# LCD.net
KiCad netlist of a schematic drawn in Altium Designer
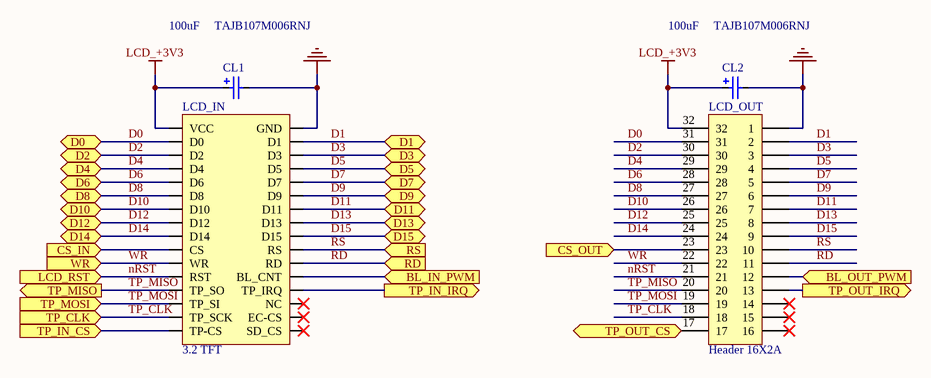
[diagram p0: LCD.SchDoc]

(export (version "E")
  (design (tool "Eeschema 10.0.6"))
  (components
    (comp (ref "CL1")
      (value "100uF     TAJB107M006RNJ")
      (footprint "CAP_TAN_B_3518")
      (description "Capacitor")
      (fields (field (name "Comment") "Cap_Tan"))
      (libsource (lib "Peace的集成库") (part "Cap_Tan"))
    )
    (comp (ref "CL2")
      (value "100uF     TAJB107M006RNJ")
      (footprint "CAP_TAN_B_3518")
      (description "Capacitor")
      (fields (field (name "Comment") "Cap_Tan"))
      (libsource (lib "Peace的集成库") (part "Cap_Tan"))
    )
    (comp (ref "LCD_IN") (value "3.2 TFT") (footprint "LCD3.2") (libsource (lib "Peace的集成库") (part "LCD3.2")))
    (comp (ref "LCD_OUT")
      (value "Header 16X2A")
      (footprint "HDR2X16_CEN")
      (description "Header, 16-Pin, Dual row")
      (fields (field (name "PUBLISHER") "Altium Limited"))
      (libsource (lib "Peace的集成库") (part "Header 16X2A"))
    )
  )
  (nets
    (net (code "1") (name "/BL_IN_PWM") (class "Default")
      (node (ref "LCD_IN") (pin "24") (pinfunction "BL_CNT_24") (pintype "passive"))
    )
    (net (code "2") (name "/BL_OUT_PWM") (class "Default")
      (node (ref "LCD_OUT") (pin "12") (pinfunction "12_12") (pintype "passive"))
    )
    (net (code "3") (name "/CS_IN") (class "Default")
      (node (ref "LCD_IN") (pin "19") (pinfunction "CS_19") (pintype "passive"))
    )
    (net (code "4") (name "/CS_OUT") (class "Default")
      (node (ref "LCD_OUT") (pin "23") (pinfunction "23_23") (pintype "passive"))
    )
    (net (code "5") (name "/D0") (class "Default")
      (node (ref "LCD_IN") (pin "3") (pinfunction "D0_3") (pintype "passive"))
      (node (ref "LCD_OUT") (pin "31") (pinfunction "31_31") (pintype "passive"))
    )
    (net (code "6") (name "/D1") (class "Default")
      (node (ref "LCD_IN") (pin "4") (pinfunction "D1_4") (pintype "passive"))
      (node (ref "LCD_OUT") (pin "2") (pinfunction "2_2") (pintype "passive"))
    )
    (net (code "7") (name "/D2") (class "Default")
      (node (ref "LCD_IN") (pin "5") (pinfunction "D2_5") (pintype "passive"))
      (node (ref "LCD_OUT") (pin "30") (pinfunction "30_30") (pintype "passive"))
    )
    (net (code "8") (name "/D3") (class "Default")
      (node (ref "LCD_IN") (pin "6") (pinfunction "D3_6") (pintype "passive"))
      (node (ref "LCD_OUT") (pin "3") (pinfunction "3_3") (pintype "passive"))
    )
    (net (code "9") (name "/D4") (class "Default")
      (node (ref "LCD_IN") (pin "7") (pinfunction "D4_7") (pintype "passive"))
      (node (ref "LCD_OUT") (pin "29") (pinfunction "29_29") (pintype "passive"))
    )
    (net (code "10") (name "/D5") (class "Default")
      (node (ref "LCD_IN") (pin "8") (pinfunction "D5_8") (pintype "passive"))
      (node (ref "LCD_OUT") (pin "4") (pinfunction "4_4") (pintype "passive"))
    )
    (net (code "11") (name "/D6") (class "Default")
      (node (ref "LCD_IN") (pin "9") (pinfunction "D6_9") (pintype "passive"))
      (node (ref "LCD_OUT") (pin "28") (pinfunction "28_28") (pintype "passive"))
    )
    (net (code "12") (name "/D7") (class "Default")
      (node (ref "LCD_IN") (pin "10") (pinfunction "D7_10") (pintype "passive"))
      (node (ref "LCD_OUT") (pin "5") (pinfunction "5_5") (pintype "passive"))
    )
    (net (code "13") (name "/D8") (class "Default")
      (node (ref "LCD_IN") (pin "11") (pinfunction "D8_11") (pintype "passive"))
      (node (ref "LCD_OUT") (pin "27") (pinfunction "27_27") (pintype "passive"))
    )
    (net (code "14") (name "/D9") (class "Default")
      (node (ref "LCD_IN") (pin "12") (pinfunction "D9_12") (pintype "passive"))
      (node (ref "LCD_OUT") (pin "6") (pinfunction "6_6") (pintype "passive"))
    )
    (net (code "15") (name "/D10") (class "Default")
      (node (ref "LCD_IN") (pin "13") (pinfunction "D10_13") (pintype "passive"))
      (node (ref "LCD_OUT") (pin "26") (pinfunction "26_26") (pintype "passive"))
    )
    (net (code "16") (name "/D11") (class "Default")
      (node (ref "LCD_IN") (pin "14") (pinfunction "D11_14") (pintype "passive"))
      (node (ref "LCD_OUT") (pin "7") (pinfunction "7_7") (pintype "passive"))
    )
    (net (code "17") (name "/D12") (class "Default")
      (node (ref "LCD_IN") (pin "15") (pinfunction "D12_15") (pintype "passive"))
      (node (ref "LCD_OUT") (pin "25") (pinfunction "25_25") (pintype "passive"))
    )
    (net (code "18") (name "/D13") (class "Default")
      (node (ref "LCD_IN") (pin "16") (pinfunction "D13_16") (pintype "passive"))
      (node (ref "LCD_OUT") (pin "8") (pinfunction "8_8") (pintype "passive"))
    )
    (net (code "19") (name "/D14") (class "Default")
      (node (ref "LCD_IN") (pin "17") (pinfunction "D14_17") (pintype "passive"))
      (node (ref "LCD_OUT") (pin "24") (pinfunction "24_24") (pintype "passive"))
    )
    (net (code "20") (name "/D15") (class "Default")
      (node (ref "LCD_IN") (pin "18") (pinfunction "D15_18") (pintype "passive"))
      (node (ref "LCD_OUT") (pin "9") (pinfunction "9_9") (pintype "passive"))
    )
    (net (code "21") (name "/RD") (class "Default")
      (node (ref "LCD_IN") (pin "22") (pinfunction "RD_22") (pintype "passive"))
      (node (ref "LCD_OUT") (pin "11") (pinfunction "11_11") (pintype "passive"))
    )
    (net (code "22") (name "/RS") (class "Default")
      (node (ref "LCD_IN") (pin "20") (pinfunction "RS_20") (pintype "passive"))
      (node (ref "LCD_OUT") (pin "10") (pinfunction "10_10") (pintype "passive"))
    )
    (net (code "23") (name "/TP_CLK") (class "Default")
      (node (ref "LCD_IN") (pin "29") (pinfunction "TP_SCK_29") (pintype "passive"))
      (node (ref "LCD_OUT") (pin "18") (pinfunction "18_18") (pintype "passive"))
    )
    (net (code "24") (name "/TP_IN_CS") (class "Default")
      (node (ref "LCD_IN") (pin "31") (pinfunction "TP-CS_31") (pintype "passive"))
    )
    (net (code "25") (name "/TP_IN_IRQ") (class "Default")
      (node (ref "LCD_IN") (pin "26") (pinfunction "TP_IRQ_26") (pintype "passive"))
    )
    (net (code "26") (name "/TP_MISO") (class "Default")
      (node (ref "LCD_IN") (pin "25") (pinfunction "TP_SO_25") (pintype "passive"))
      (node (ref "LCD_OUT") (pin "20") (pinfunction "20_20") (pintype "passive"))
    )
    (net (code "27") (name "/TP_MOSI") (class "Default")
      (node (ref "LCD_IN") (pin "27") (pinfunction "TP_SI_27") (pintype "passive"))
      (node (ref "LCD_OUT") (pin "19") (pinfunction "19_19") (pintype "passive"))
    )
    (net (code "28") (name "/TP_OUT_CS") (class "Default")
      (node (ref "LCD_OUT") (pin "17") (pinfunction "17_17") (pintype "passive"))
    )
    (net (code "29") (name "/TP_OUT_IRQ") (class "Default")
      (node (ref "LCD_OUT") (pin "13") (pinfunction "13_13") (pintype "passive"))
    )
    (net (code "30") (name "/WR") (class "Default")
      (node (ref "LCD_IN") (pin "21") (pinfunction "WR_21") (pintype "passive"))
      (node (ref "LCD_OUT") (pin "22") (pinfunction "22_22") (pintype "passive"))
    )
    (net (code "31") (name "/nRST") (class "Default")
      (node (ref "LCD_IN") (pin "23") (pinfunction "RST_23") (pintype "passive"))
      (node (ref "LCD_OUT") (pin "21") (pinfunction "21_21") (pintype "passive"))
    )
    (net (code "32") (name "GND") (class "Default")
      (node (ref "CL1") (pin "2") (pinfunction "2_2") (pintype "passive"))
      (node (ref "CL2") (pin "2") (pinfunction "2_2") (pintype "passive"))
      (node (ref "LCD_IN") (pin "2") (pinfunction "GND_2") (pintype "passive"))
      (node (ref "LCD_OUT") (pin "1") (pinfunction "1_1") (pintype "passive"))
    )
    (net (code "33") (name "LCD_+3V3") (class "Default")
      (node (ref "CL1") (pin "1") (pinfunction "1_1") (pintype "passive"))
      (node (ref "CL2") (pin "1") (pinfunction "1_1") (pintype "passive"))
      (node (ref "LCD_IN") (pin "1") (pinfunction "VCC_1") (pintype "passive"))
      (node (ref "LCD_OUT") (pin "32") (pinfunction "32_32") (pintype "passive"))
    )
    (net (code "34") (name "unconnected-(LCD_IN-EC-CS-Pad30)") (class "Default")
      (node (ref "LCD_IN") (pin "30") (pinfunction "EC-CS_30") (pintype "passive+no_connect"))
    )
    (net (code "35") (name "unconnected-(LCD_IN-NC-Pad28)") (class "Default")
      (node (ref "LCD_IN") (pin "28") (pinfunction "NC_28") (pintype "passive+no_connect"))
    )
    (net (code "36") (name "unconnected-(LCD_IN-SD_CS-Pad32)") (class "Default")
      (node (ref "LCD_IN") (pin "32") (pinfunction "SD_CS_32") (pintype "passive+no_connect"))
    )
    (net (code "37") (name "unconnected-(LCD_OUT-Pad14)") (class "Default")
      (node (ref "LCD_OUT") (pin "14") (pinfunction "14_14") (pintype "passive+no_connect"))
    )
    (net (code "38") (name "unconnected-(LCD_OUT-Pad15)") (class "Default")
      (node (ref "LCD_OUT") (pin "15") (pinfunction "15_15") (pintype "passive+no_connect"))
    )
    (net (code "39") (name "unconnected-(LCD_OUT-Pad16)") (class "Default")
      (node (ref "LCD_OUT") (pin "16") (pinfunction "16_16") (pintype "passive+no_connect"))
    )
  )
)
